# SubBus3.net
KiCad netlist of a schematic drawn in Altium Designer
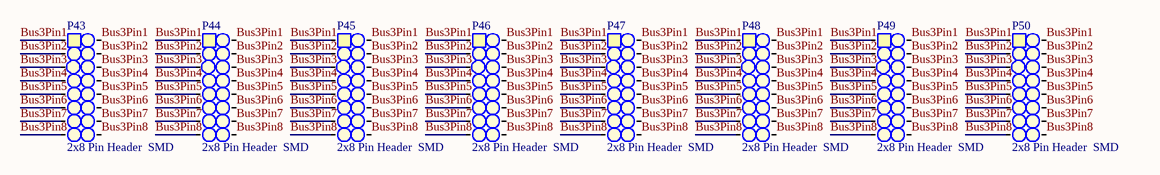
[diagram p0: SubBus3.SchDoc]

(export (version "E")
  (design (tool "Eeschema 10.0.6"))
  (components
    (comp (ref "P43")
      (value "2x8 Pin Header  SMD")
      (footprint "2X8_SMD_PH_2.54")
      (description "2.54mm, SMD")
      (libsource (lib "jclib") (part "2x8 Pin Header  SMD"))
    )
    (comp (ref "P44")
      (value "2x8 Pin Header  SMD")
      (footprint "2X8_SMD_PH_2.54")
      (description "2.54mm, SMD")
      (libsource (lib "jclib") (part "2x8 Pin Header  SMD"))
    )
    (comp (ref "P45")
      (value "2x8 Pin Header  SMD")
      (footprint "2X8_SMD_PH_2.54")
      (description "2.54mm, SMD")
      (libsource (lib "jclib") (part "2x8 Pin Header  SMD"))
    )
    (comp (ref "P46")
      (value "2x8 Pin Header  SMD")
      (footprint "2X8_SMD_PH_2.54")
      (description "2.54mm, SMD")
      (libsource (lib "jclib") (part "2x8 Pin Header  SMD"))
    )
    (comp (ref "P47")
      (value "2x8 Pin Header  SMD")
      (footprint "2X8_SMD_PH_2.54")
      (description "2.54mm, SMD")
      (libsource (lib "jclib") (part "2x8 Pin Header  SMD"))
    )
    (comp (ref "P48")
      (value "2x8 Pin Header  SMD")
      (footprint "2X8_SMD_PH_2.54")
      (description "2.54mm, SMD")
      (libsource (lib "jclib") (part "2x8 Pin Header  SMD"))
    )
    (comp (ref "P49")
      (value "2x8 Pin Header  SMD")
      (footprint "2X8_SMD_PH_2.54")
      (description "2.54mm, SMD")
      (libsource (lib "jclib") (part "2x8 Pin Header  SMD"))
    )
    (comp (ref "P50")
      (value "2x8 Pin Header  SMD")
      (footprint "2X8_SMD_PH_2.54")
      (description "2.54mm, SMD")
      (libsource (lib "jclib") (part "2x8 Pin Header  SMD"))
    )
  )
  (nets
    (net (code "1") (name "/Bus3Pin1") (class "Default")
      (node (ref "P43") (pin "1") (pinfunction "1_1") (pintype "passive"))
      (node (ref "P43") (pin "16") (pinfunction "16_16") (pintype "passive"))
      (node (ref "P44") (pin "1") (pinfunction "1_1") (pintype "passive"))
      (node (ref "P44") (pin "16") (pinfunction "16_16") (pintype "passive"))
      (node (ref "P45") (pin "1") (pinfunction "1_1") (pintype "passive"))
      (node (ref "P45") (pin "16") (pinfunction "16_16") (pintype "passive"))
      (node (ref "P46") (pin "1") (pinfunction "1_1") (pintype "passive"))
      (node (ref "P46") (pin "16") (pinfunction "16_16") (pintype "passive"))
      (node (ref "P47") (pin "1") (pinfunction "1_1") (pintype "passive"))
      (node (ref "P47") (pin "16") (pinfunction "16_16") (pintype "passive"))
      (node (ref "P48") (pin "1") (pinfunction "1_1") (pintype "passive"))
      (node (ref "P48") (pin "16") (pinfunction "16_16") (pintype "passive"))
      (node (ref "P49") (pin "1") (pinfunction "1_1") (pintype "passive"))
      (node (ref "P49") (pin "16") (pinfunction "16_16") (pintype "passive"))
      (node (ref "P50") (pin "1") (pinfunction "1_1") (pintype "passive"))
      (node (ref "P50") (pin "16") (pinfunction "16_16") (pintype "passive"))
    )
    (net (code "2") (name "/Bus3Pin2") (class "Default")
      (node (ref "P43") (pin "15") (pinfunction "15_15") (pintype "passive"))
      (node (ref "P43") (pin "2") (pinfunction "2_2") (pintype "passive"))
      (node (ref "P44") (pin "15") (pinfunction "15_15") (pintype "passive"))
      (node (ref "P44") (pin "2") (pinfunction "2_2") (pintype "passive"))
      (node (ref "P45") (pin "15") (pinfunction "15_15") (pintype "passive"))
      (node (ref "P45") (pin "2") (pinfunction "2_2") (pintype "passive"))
      (node (ref "P46") (pin "15") (pinfunction "15_15") (pintype "passive"))
      (node (ref "P46") (pin "2") (pinfunction "2_2") (pintype "passive"))
      (node (ref "P47") (pin "15") (pinfunction "15_15") (pintype "passive"))
      (node (ref "P47") (pin "2") (pinfunction "2_2") (pintype "passive"))
      (node (ref "P48") (pin "15") (pinfunction "15_15") (pintype "passive"))
      (node (ref "P48") (pin "2") (pinfunction "2_2") (pintype "passive"))
      (node (ref "P49") (pin "15") (pinfunction "15_15") (pintype "passive"))
      (node (ref "P49") (pin "2") (pinfunction "2_2") (pintype "passive"))
      (node (ref "P50") (pin "15") (pinfunction "15_15") (pintype "passive"))
      (node (ref "P50") (pin "2") (pinfunction "2_2") (pintype "passive"))
    )
    (net (code "3") (name "/Bus3Pin3") (class "Default")
      (node (ref "P43") (pin "14") (pinfunction "14_14") (pintype "passive"))
      (node (ref "P43") (pin "3") (pinfunction "3_3") (pintype "passive"))
      (node (ref "P44") (pin "14") (pinfunction "14_14") (pintype "passive"))
      (node (ref "P44") (pin "3") (pinfunction "3_3") (pintype "passive"))
      (node (ref "P45") (pin "14") (pinfunction "14_14") (pintype "passive"))
      (node (ref "P45") (pin "3") (pinfunction "3_3") (pintype "passive"))
      (node (ref "P46") (pin "14") (pinfunction "14_14") (pintype "passive"))
      (node (ref "P46") (pin "3") (pinfunction "3_3") (pintype "passive"))
      (node (ref "P47") (pin "14") (pinfunction "14_14") (pintype "passive"))
      (node (ref "P47") (pin "3") (pinfunction "3_3") (pintype "passive"))
      (node (ref "P48") (pin "14") (pinfunction "14_14") (pintype "passive"))
      (node (ref "P48") (pin "3") (pinfunction "3_3") (pintype "passive"))
      (node (ref "P49") (pin "14") (pinfunction "14_14") (pintype "passive"))
      (node (ref "P49") (pin "3") (pinfunction "3_3") (pintype "passive"))
      (node (ref "P50") (pin "14") (pinfunction "14_14") (pintype "passive"))
      (node (ref "P50") (pin "3") (pinfunction "3_3") (pintype "passive"))
    )
    (net (code "4") (name "/Bus3Pin4") (class "Default")
      (node (ref "P43") (pin "13") (pinfunction "13_13") (pintype "passive"))
      (node (ref "P43") (pin "4") (pinfunction "4_4") (pintype "passive"))
      (node (ref "P44") (pin "13") (pinfunction "13_13") (pintype "passive"))
      (node (ref "P44") (pin "4") (pinfunction "4_4") (pintype "passive"))
      (node (ref "P45") (pin "13") (pinfunction "13_13") (pintype "passive"))
      (node (ref "P45") (pin "4") (pinfunction "4_4") (pintype "passive"))
      (node (ref "P46") (pin "13") (pinfunction "13_13") (pintype "passive"))
      (node (ref "P46") (pin "4") (pinfunction "4_4") (pintype "passive"))
      (node (ref "P47") (pin "13") (pinfunction "13_13") (pintype "passive"))
      (node (ref "P47") (pin "4") (pinfunction "4_4") (pintype "passive"))
      (node (ref "P48") (pin "13") (pinfunction "13_13") (pintype "passive"))
      (node (ref "P48") (pin "4") (pinfunction "4_4") (pintype "passive"))
      (node (ref "P49") (pin "13") (pinfunction "13_13") (pintype "passive"))
      (node (ref "P49") (pin "4") (pinfunction "4_4") (pintype "passive"))
      (node (ref "P50") (pin "13") (pinfunction "13_13") (pintype "passive"))
      (node (ref "P50") (pin "4") (pinfunction "4_4") (pintype "passive"))
    )
    (net (code "5") (name "/Bus3Pin5") (class "Default")
      (node (ref "P43") (pin "12") (pinfunction "12_12") (pintype "passive"))
      (node (ref "P43") (pin "5") (pinfunction "5_5") (pintype "passive"))
      (node (ref "P44") (pin "12") (pinfunction "12_12") (pintype "passive"))
      (node (ref "P44") (pin "5") (pinfunction "5_5") (pintype "passive"))
      (node (ref "P45") (pin "12") (pinfunction "12_12") (pintype "passive"))
      (node (ref "P45") (pin "5") (pinfunction "5_5") (pintype "passive"))
      (node (ref "P46") (pin "12") (pinfunction "12_12") (pintype "passive"))
      (node (ref "P46") (pin "5") (pinfunction "5_5") (pintype "passive"))
      (node (ref "P47") (pin "12") (pinfunction "12_12") (pintype "passive"))
      (node (ref "P47") (pin "5") (pinfunction "5_5") (pintype "passive"))
      (node (ref "P48") (pin "12") (pinfunction "12_12") (pintype "passive"))
      (node (ref "P48") (pin "5") (pinfunction "5_5") (pintype "passive"))
      (node (ref "P49") (pin "12") (pinfunction "12_12") (pintype "passive"))
      (node (ref "P49") (pin "5") (pinfunction "5_5") (pintype "passive"))
      (node (ref "P50") (pin "12") (pinfunction "12_12") (pintype "passive"))
      (node (ref "P50") (pin "5") (pinfunction "5_5") (pintype "passive"))
    )
    (net (code "6") (name "/Bus3Pin6") (class "Default")
      (node (ref "P43") (pin "11") (pinfunction "11_11") (pintype "passive"))
      (node (ref "P43") (pin "6") (pinfunction "6_6") (pintype "passive"))
      (node (ref "P44") (pin "11") (pinfunction "11_11") (pintype "passive"))
      (node (ref "P44") (pin "6") (pinfunction "6_6") (pintype "passive"))
      (node (ref "P45") (pin "11") (pinfunction "11_11") (pintype "passive"))
      (node (ref "P45") (pin "6") (pinfunction "6_6") (pintype "passive"))
      (node (ref "P46") (pin "11") (pinfunction "11_11") (pintype "passive"))
      (node (ref "P46") (pin "6") (pinfunction "6_6") (pintype "passive"))
      (node (ref "P47") (pin "11") (pinfunction "11_11") (pintype "passive"))
      (node (ref "P47") (pin "6") (pinfunction "6_6") (pintype "passive"))
      (node (ref "P48") (pin "11") (pinfunction "11_11") (pintype "passive"))
      (node (ref "P48") (pin "6") (pinfunction "6_6") (pintype "passive"))
      (node (ref "P49") (pin "11") (pinfunction "11_11") (pintype "passive"))
      (node (ref "P49") (pin "6") (pinfunction "6_6") (pintype "passive"))
      (node (ref "P50") (pin "11") (pinfunction "11_11") (pintype "passive"))
      (node (ref "P50") (pin "6") (pinfunction "6_6") (pintype "passive"))
    )
    (net (code "7") (name "/Bus3Pin7") (class "Default")
      (node (ref "P43") (pin "10") (pinfunction "10_10") (pintype "passive"))
      (node (ref "P43") (pin "7") (pinfunction "7_7") (pintype "passive"))
      (node (ref "P44") (pin "10") (pinfunction "10_10") (pintype "passive"))
      (node (ref "P44") (pin "7") (pinfunction "7_7") (pintype "passive"))
      (node (ref "P45") (pin "10") (pinfunction "10_10") (pintype "passive"))
      (node (ref "P45") (pin "7") (pinfunction "7_7") (pintype "passive"))
      (node (ref "P46") (pin "10") (pinfunction "10_10") (pintype "passive"))
      (node (ref "P46") (pin "7") (pinfunction "7_7") (pintype "passive"))
      (node (ref "P47") (pin "10") (pinfunction "10_10") (pintype "passive"))
      (node (ref "P47") (pin "7") (pinfunction "7_7") (pintype "passive"))
      (node (ref "P48") (pin "10") (pinfunction "10_10") (pintype "passive"))
      (node (ref "P48") (pin "7") (pinfunction "7_7") (pintype "passive"))
      (node (ref "P49") (pin "10") (pinfunction "10_10") (pintype "passive"))
      (node (ref "P49") (pin "7") (pinfunction "7_7") (pintype "passive"))
      (node (ref "P50") (pin "10") (pinfunction "10_10") (pintype "passive"))
      (node (ref "P50") (pin "7") (pinfunction "7_7") (pintype "passive"))
    )
    (net (code "8") (name "/Bus3Pin8") (class "Default")
      (node (ref "P43") (pin "8") (pinfunction "8_8") (pintype "passive"))
      (node (ref "P43") (pin "9") (pinfunction "9_9") (pintype "passive"))
      (node (ref "P44") (pin "8") (pinfunction "8_8") (pintype "passive"))
      (node (ref "P44") (pin "9") (pinfunction "9_9") (pintype "passive"))
      (node (ref "P45") (pin "8") (pinfunction "8_8") (pintype "passive"))
      (node (ref "P45") (pin "9") (pinfunction "9_9") (pintype "passive"))
      (node (ref "P46") (pin "8") (pinfunction "8_8") (pintype "passive"))
      (node (ref "P46") (pin "9") (pinfunction "9_9") (pintype "passive"))
      (node (ref "P47") (pin "8") (pinfunction "8_8") (pintype "passive"))
      (node (ref "P47") (pin "9") (pinfunction "9_9") (pintype "passive"))
      (node (ref "P48") (pin "8") (pinfunction "8_8") (pintype "passive"))
      (node (ref "P48") (pin "9") (pinfunction "9_9") (pintype "passive"))
      (node (ref "P49") (pin "8") (pinfunction "8_8") (pintype "passive"))
      (node (ref "P49") (pin "9") (pinfunction "9_9") (pintype "passive"))
      (node (ref "P50") (pin "8") (pinfunction "8_8") (pintype "passive"))
      (node (ref "P50") (pin "9") (pinfunction "9_9") (pintype "passive"))
    )
  )
)
